# PSAS_Safety_System.net
KiCad netlist of a schematic drawn in EAGLE
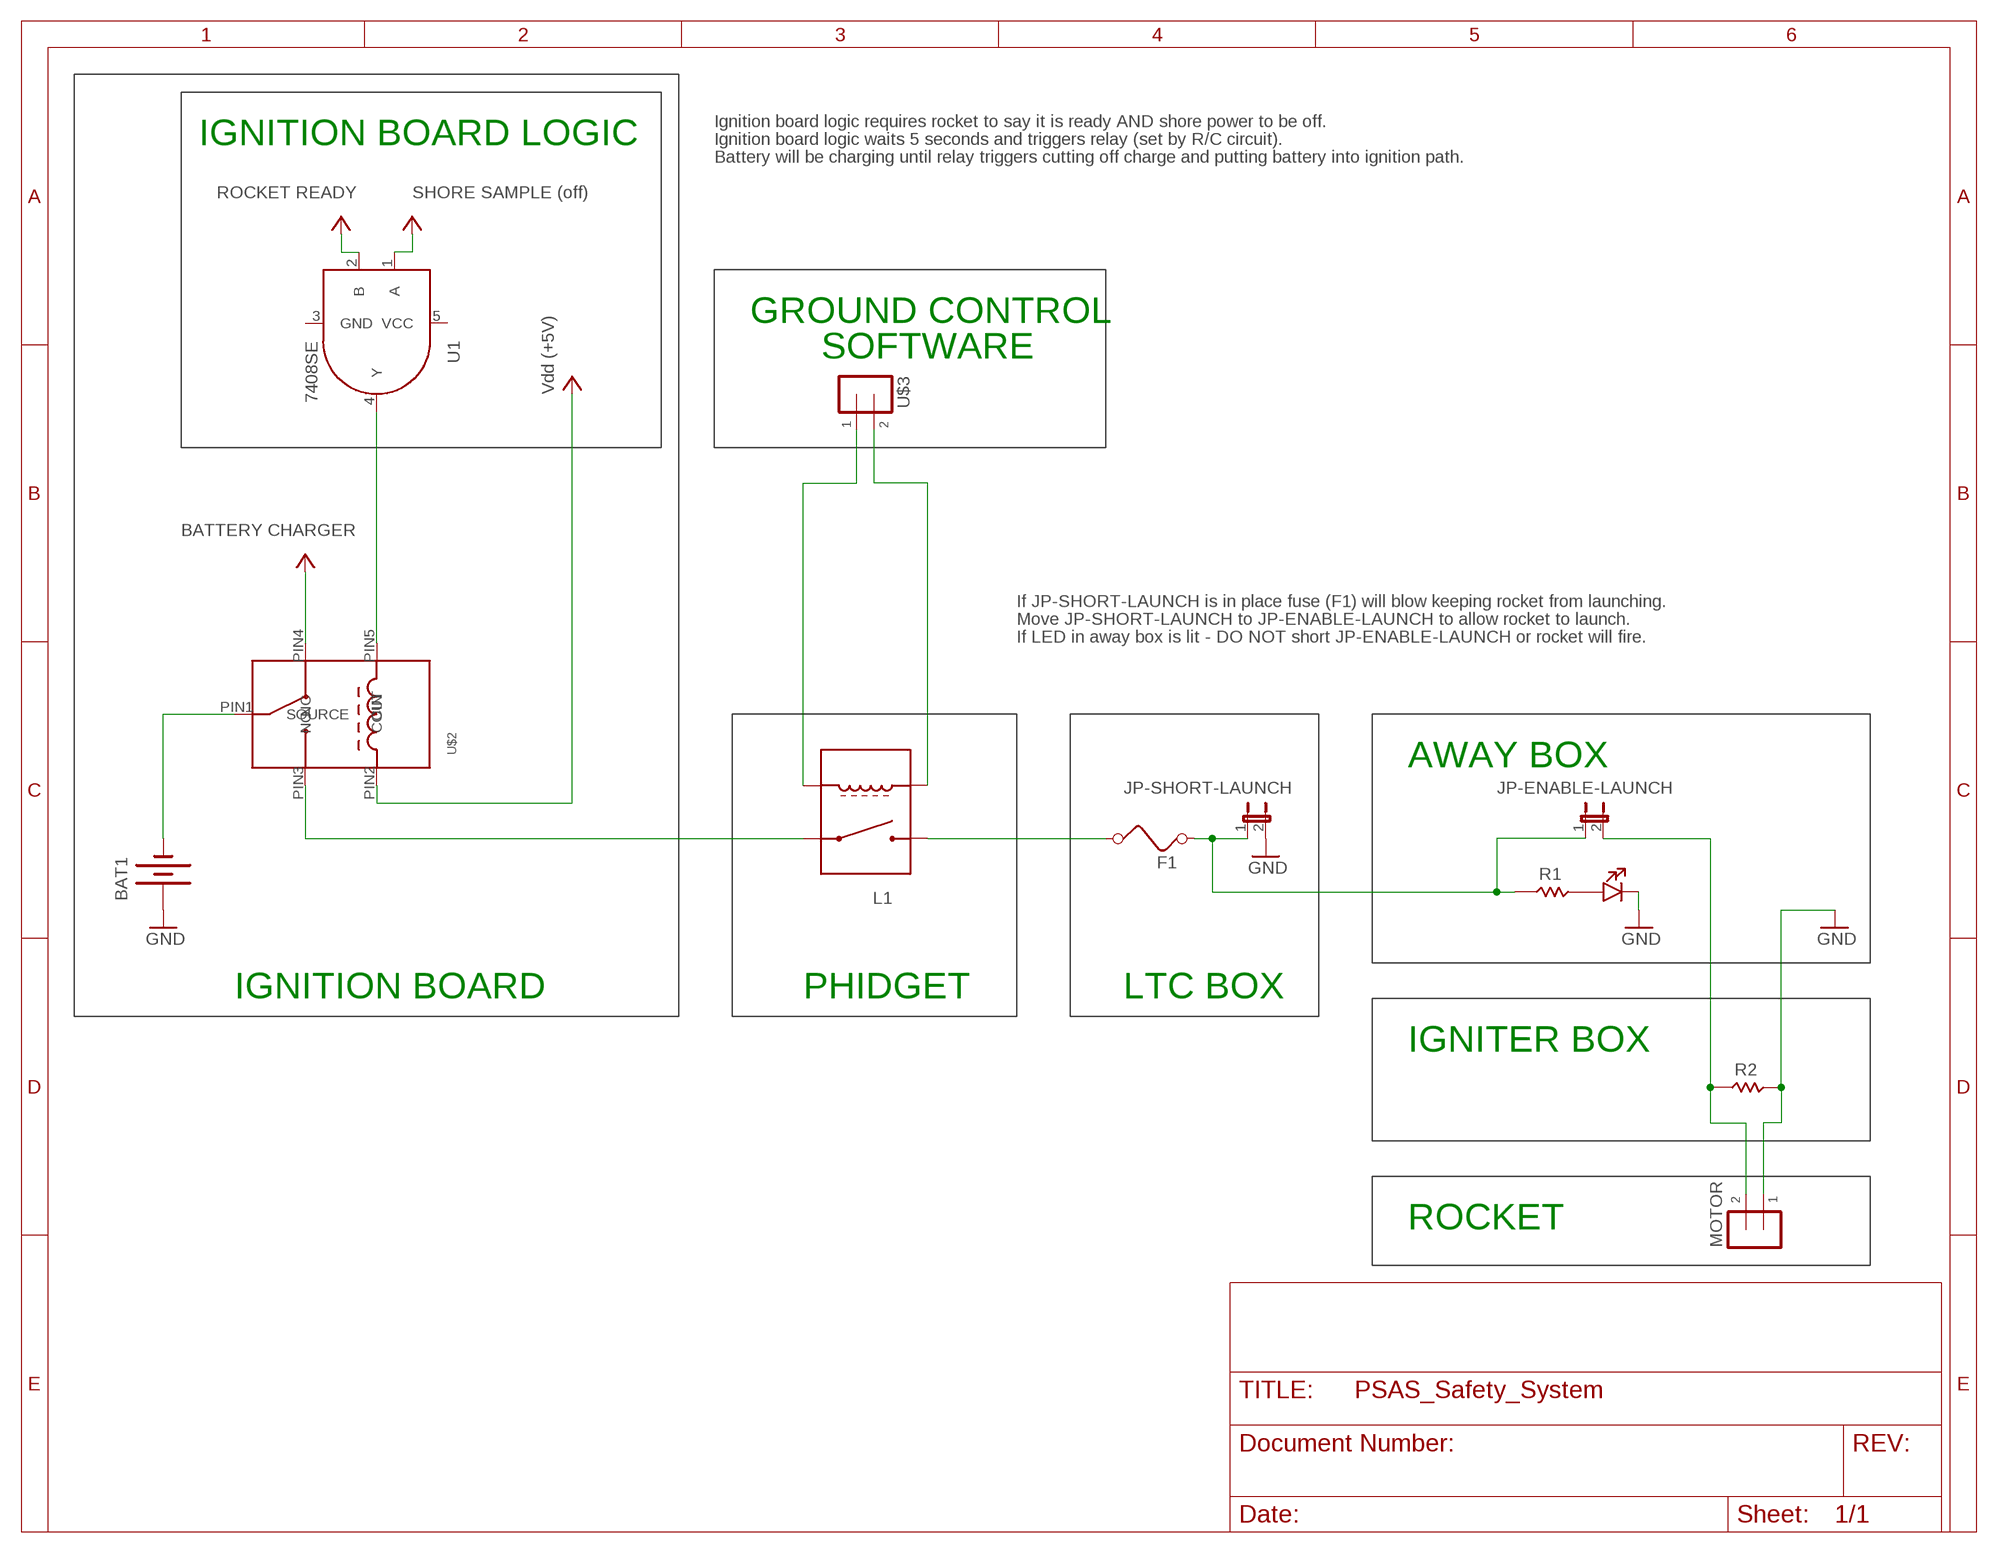
[diagram p0: schematic, sheet 1]

(export (version "E")
  (design (tool "Eeschema 10.0.6"))
  (components
    (comp (ref "BAT1")
      (value "BATTERY12MM")
      (footprint "eagle-import:BATTCON_12MM")
      (libsource (lib "eagle-import") (part "BATTERY12MM"))
    )
    (comp (ref "F1")
      (value "FUSE")
      (footprint "eagle-import:FUSE")
      (libsource (lib "eagle-import") (part "FUSE"))
    )
    (comp (ref "JP-ENABLE-LAUNCH")
      (value "JP1E")
      (footprint "eagle-import:JP1")
      (libsource (lib "eagle-import") (part "JP1E"))
    )
    (comp (ref "JP-SHORT-LAUNCH")
      (value "JP1E")
      (footprint "eagle-import:JP1")
      (libsource (lib "eagle-import") (part "JP1E"))
    )
    (comp (ref "L1")
      (value "RELAY")
      (footprint "eagle-import:G5T-1A")
      (libsource (lib "eagle-import") (part "RELAY"))
    )
    (comp (ref "MOTOR")
      (value "SCREW-TERMINAL-5MM")
      (footprint "eagle-import:SCREW-TERM-5MM")
      (libsource (lib "eagle-import") (part "SCREW-TERMINAL-5MM"))
    )
    (comp (ref "R1")
      (value "RESISTOR-0805")
      (footprint "eagle-import:0805")
      (libsource (lib "eagle-import") (part "RESISTOR-0805"))
    )
    (comp (ref "R2")
      (value "RESISTOR-0805")
      (footprint "eagle-import:0805")
      (libsource (lib "eagle-import") (part "RESISTOR-0805"))
    )
    (comp (ref "U$1")
      (value "LED-550-XX04")
      (footprint "eagle-import:LED-550")
      (libsource (lib "eagle-import") (part "LED-550-XX04"))
    )
    (comp (ref "U$2")
      (value "RELAY-2")
      (footprint "eagle-import:G5LA")
      (libsource (lib "eagle-import") (part "RELAY-2"))
    )
    (comp (ref "U$3")
      (value "SCREW-TERMINAL-5MM")
      (footprint "eagle-import:SCREW-TERM-5MM")
      (libsource (lib "eagle-import") (part "SCREW-TERMINAL-5MM"))
    )
    (comp (ref "U1")
      (value "7408SE")
      (footprint "eagle-import:SOT353")
      (libsource (lib "eagle-import") (part "7408SE"))
    )
  )
  (nets
    (net (code "1") (name "BATTERY CHARGER") (class "Default")
      (node (ref "U$2") (pin "PIN2") (pinfunction "COUT_PIN2") (pintype "bidirectional"))
      (node (ref "U$2") (pin "PIN4") (pinfunction "NC_PIN4") (pintype "bidirectional"))
      (node (ref "U1") (pin "1") (pinfunction "A_1") (pintype "bidirectional"))
      (node (ref "U1") (pin "2") (pinfunction "B_2") (pintype "bidirectional"))
    )
    (net (code "2") (name "GND") (class "Default")
      (node (ref "BAT1") (pin "PWR@1") (pinfunction "+_PWR@1") (pintype "power_in"))
      (node (ref "JP-SHORT-LAUNCH") (pin "2") (pinfunction "2_2") (pintype "passive"))
      (node (ref "MOTOR") (pin "1") (pinfunction "1_1") (pintype "passive"))
      (node (ref "R2") (pin "CATHODE") (pinfunction "CATHODE_CATHODE") (pintype "bidirectional"))
      (node (ref "U$1") (pin "CATHODE") (pinfunction "CATHODE_CATHODE") (pintype "bidirectional"))
    )
    (net (code "3") (name "Net-(BAT1--)") (class "Default")
      (node (ref "BAT1") (pin "GND") (pinfunction "-_GND") (pintype "power_in"))
      (node (ref "U$2") (pin "PIN1") (pinfunction "SOURCE_PIN1") (pintype "bidirectional"))
    )
    (net (code "4") (name "Net-(F1-Pad1)") (class "Default")
      (node (ref "F1") (pin "1") (pinfunction "1_1") (pintype "passive"))
      (node (ref "JP-ENABLE-LAUNCH") (pin "1") (pinfunction "1_1") (pintype "passive"))
      (node (ref "JP-SHORT-LAUNCH") (pin "1") (pinfunction "1_1") (pintype "passive"))
      (node (ref "R1") (pin "ANODE") (pinfunction "ANODE_ANODE") (pintype "bidirectional"))
    )
    (net (code "5") (name "Net-(F1-Pad2)") (class "Default")
      (node (ref "F1") (pin "2") (pinfunction "2_2") (pintype "passive"))
      (node (ref "L1") (pin "SW2") (pinfunction "SW2_SW2") (pintype "bidirectional"))
    )
    (net (code "6") (name "Net-(JP-ENABLE-LAUNCH-Pad2)") (class "Default")
      (node (ref "JP-ENABLE-LAUNCH") (pin "2") (pinfunction "2_2") (pintype "passive"))
      (node (ref "MOTOR") (pin "2") (pinfunction "2_2") (pintype "passive"))
      (node (ref "R2") (pin "ANODE") (pinfunction "ANODE_ANODE") (pintype "bidirectional"))
    )
    (net (code "7") (name "Net-(L1-PadCIN)") (class "Default")
      (node (ref "L1") (pin "CIN") (pinfunction "CIN_CIN") (pintype "bidirectional"))
      (node (ref "U$3") (pin "1") (pinfunction "1_1") (pintype "passive"))
    )
    (net (code "8") (name "Net-(L1-PadCOUT)") (class "Default")
      (node (ref "L1") (pin "COUT") (pinfunction "COUT_COUT") (pintype "bidirectional"))
      (node (ref "U$3") (pin "2") (pinfunction "2_2") (pintype "passive"))
    )
    (net (code "9") (name "Net-(R1-PadCATHODE)") (class "Default")
      (node (ref "R1") (pin "CATHODE") (pinfunction "CATHODE_CATHODE") (pintype "bidirectional"))
      (node (ref "U$1") (pin "ANODE") (pinfunction "ANODE_ANODE") (pintype "bidirectional"))
    )
    (net (code "10") (name "Net-(U$2-CIN)") (class "Default")
      (node (ref "U$2") (pin "PIN5") (pinfunction "CIN_PIN5") (pintype "bidirectional"))
      (node (ref "U1") (pin "4") (pinfunction "Y_4") (pintype "bidirectional"))
    )
    (net (code "11") (name "Net-(U$2-NO)") (class "Default")
      (node (ref "L1") (pin "SW1") (pinfunction "SW1_SW1") (pintype "bidirectional"))
      (node (ref "U$2") (pin "PIN3") (pinfunction "NO_PIN3") (pintype "bidirectional"))
    )
    (net (code "12") (name "unconnected-(U1-GND-Pad3)") (class "Default")
      (node (ref "U1") (pin "3") (pinfunction "GND_3") (pintype "bidirectional"))
    )
    (net (code "13") (name "unconnected-(U1-VCC-Pad5)") (class "Default")
      (node (ref "U1") (pin "5") (pinfunction "VCC_5") (pintype "bidirectional"))
    )
  )
)
